# Game_Consol_Power.net
KiCad netlist of a schematic drawn in Altium Designer
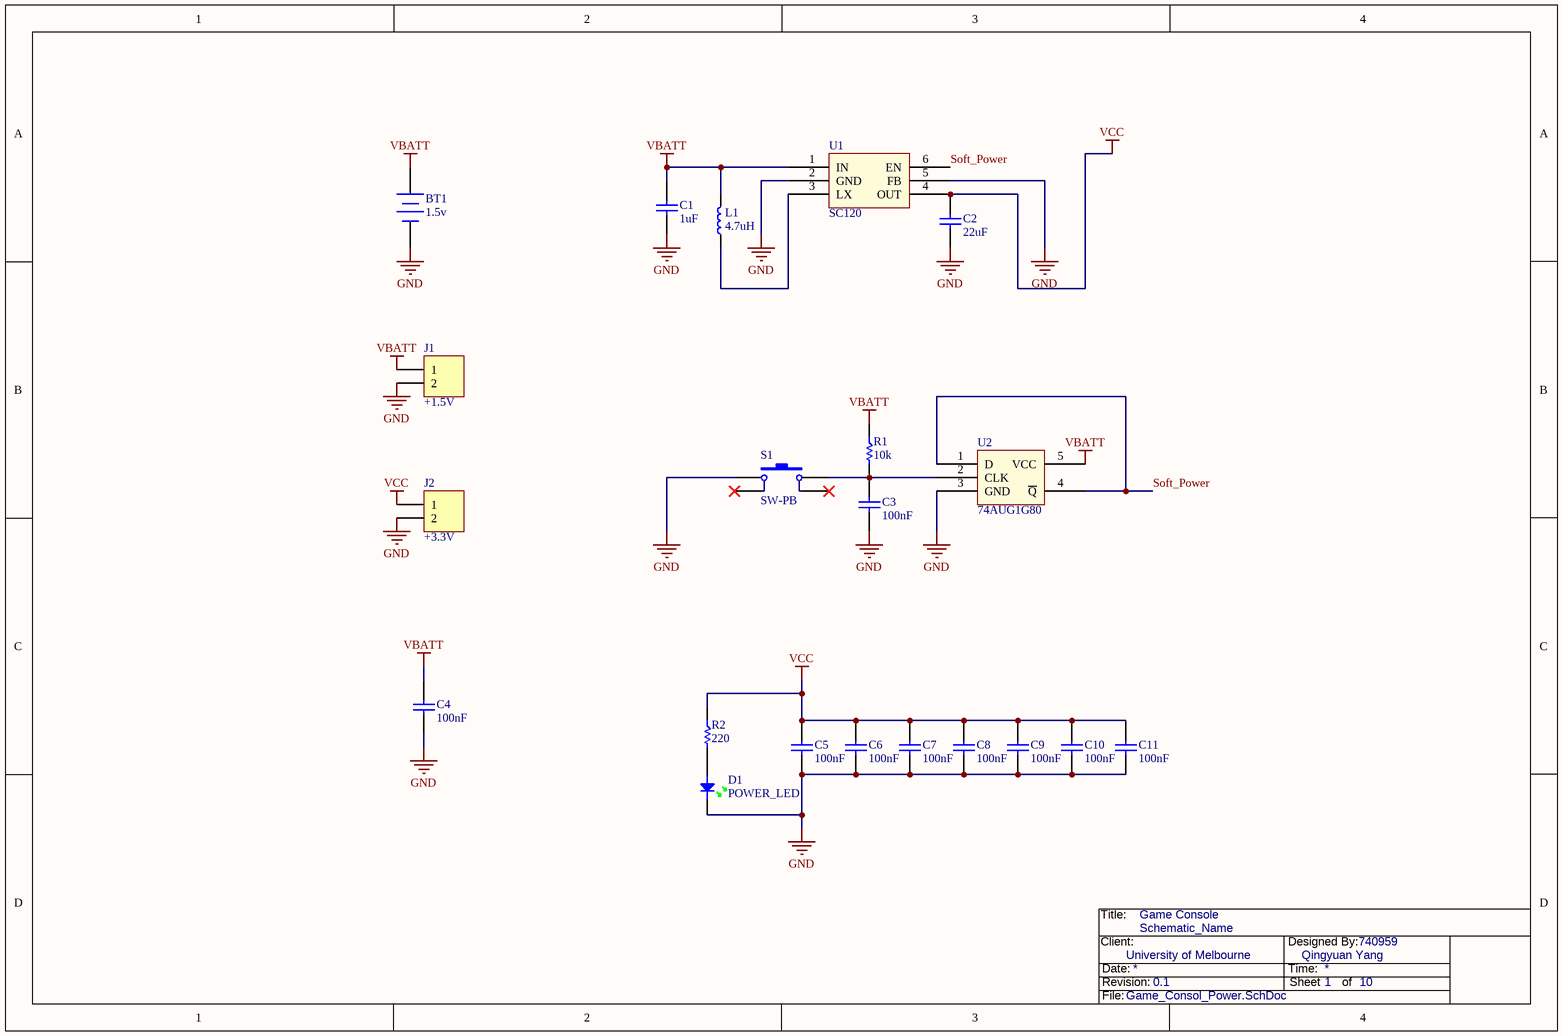
[diagram p0: Game_Consol_Power.SchDoc]

(export (version "E")
  (design (tool "Eeschema 10.0.6"))
  (components
    (comp (ref "BT1")
      (value "1.5v")
      (footprint "BATT_HOLDER")
      (description "Battery Holder AA 1.5v")
      (fields (field (name "PUBLISHER") "Altium Limited"))
      (libsource (lib "EmbSD Lib 0v1") (part "BAT"))
    )
    (comp (ref "C1")
      (value "1uF")
      (footprint "0805")
      (description "Capacitor 100nF")
      (libsource (lib "EmbSD Lib 0v1") (part "C 0805"))
    )
    (comp (ref "C2")
      (value "22uF")
      (footprint "1210")
      (description "Capacitor 22uF")
      (fields
        (field (name "MANUFACTURER") "Generic Components")
        (field (name "MANUFACTURER PART NUMBER") "LMK316F226ZL-T")
        (field (name "PUBLISHER") "Altium Limited")
      )
      (libsource (lib "EmbSD Lib 0v1") (part "C 1210"))
    )
    (comp (ref "C3")
      (value "100nF")
      (footprint "0805")
      (description "Capacitor 100nF")
      (libsource (lib "EmbSD Lib 0v1") (part "C 0805"))
    )
    (comp (ref "C4")
      (value "100nF")
      (footprint "0805")
      (description "Capacitor 100nF")
      (libsource (lib "EmbSD Lib 0v1") (part "C 0805"))
    )
    (comp (ref "C5")
      (value "100nF")
      (footprint "0805")
      (description "Capacitor 100nF")
      (libsource (lib "EmbSD Lib 0v1") (part "C 0805"))
    )
    (comp (ref "C6")
      (value "100nF")
      (footprint "0805")
      (description "Capacitor 100nF")
      (libsource (lib "EmbSD Lib 0v1") (part "C 0805"))
    )
    (comp (ref "C7")
      (value "100nF")
      (footprint "0805")
      (description "Capacitor 100nF")
      (libsource (lib "EmbSD Lib 0v1") (part "C 0805"))
    )
    (comp (ref "C8")
      (value "100nF")
      (footprint "0805")
      (description "Capacitor 100nF")
      (libsource (lib "EmbSD Lib 0v1") (part "C 0805"))
    )
    (comp (ref "C9")
      (value "100nF")
      (footprint "0805")
      (description "Capacitor 100nF")
      (libsource (lib "EmbSD Lib 0v1") (part "C 0805"))
    )
    (comp (ref "C10")
      (value "100nF")
      (footprint "0805")
      (description "Capacitor 100nF")
      (libsource (lib "EmbSD Lib 0v1") (part "C 0805"))
    )
    (comp (ref "C11")
      (value "100nF")
      (footprint "0805")
      (description "Capacitor 100nF")
      (libsource (lib "EmbSD Lib 0v1") (part "C 0805"))
    )
    (comp (ref "D1")
      (value "POWER_LED")
      (footprint "0805D")
      (description "Light Emitting Diode")
      (fields (field (name "MANUFACTURER") "Generic Components") (field (name "PUBLISHER") "Altium Limited"))
      (libsource (lib "EmbSD Lib 0v1") (part "LED GREEN"))
    )
    (comp (ref "J1")
      (value "+1.5V")
      (footprint "HDR1X2")
      (description "Header, 2-Pin")
      (fields (field (name "PUBLISHER") "Altium Limited"))
      (libsource (lib "Miscellaneous Connectors") (part "Header 2"))
    )
    (comp (ref "J2")
      (value "+3.3V")
      (footprint "HDR1X2")
      (description "Header, 2-Pin")
      (fields (field (name "PUBLISHER") "Altium Limited"))
      (libsource (lib "Miscellaneous Connectors") (part "Header 2"))
    )
    (comp (ref "L1")
      (value "4.7uH")
      (footprint "1210L")
      (description "Inductor 4.7uH")
      (fields
        (field (name "MANUFACTURER") "Murata Electronics North America")
        (field (name "MANUFACTURER PART NUMBER") "LQH32CN4R7M23L")
        (field (name "PUBLISHER") "Altium Limited")
      )
      (libsource (lib "EmbSD Lib 0v1") (part "I 1210"))
    )
    (comp (ref "R1")
      (value "10k")
      (footprint "0805")
      (description "Resistor")
      (libsource (lib "EmbSD Lib 0v1") (part "R"))
    )
    (comp (ref "R2")
      (value "220")
      (footprint "0805")
      (description "Resistor")
      (libsource (lib "EmbSD Lib 0v1") (part "R"))
    )
    (comp (ref "S1")
      (value "SW-PB")
      (footprint "SPNO_SMD")
      (description "Push Button Switch")
      (fields
        (field (name "MANUFACTURER") "TE Connectivity")
        (field (name "MANUFACTURER PART NUMBER") "FSM4JSMA")
        (field (name "PUBLISHER") "Altium Limited")
      )
      (libsource (lib "EmbSD Lib 0v1") (part "SW-PB"))
    )
    (comp (ref "U1")
      (value "SC120")
      (footprint "SOT23-6")
      (description "Regulator Low Voltage")
      (libsource (lib "EmbSD Lib 0v1") (part "SC120"))
    )
    (comp (ref "U2")
      (value "74AUG1G80")
      (footprint "SOT23-5")
      (description "Inverted single D flip flop")
      (libsource (lib "EmbSD Lib 0v1") (part "74AUG1G80"))
    )
  )
  (nets
    (net (code "1") (name "/Soft_Power") (class "Default")
      (node (ref "U1") (pin "6") (pinfunction "EN_6") (pintype "passive"))
      (node (ref "U2") (pin "1") (pinfunction "D_1") (pintype "passive"))
      (node (ref "U2") (pin "4") (pinfunction "~{Q}_4") (pintype "passive"))
    )
    (net (code "2") (name "GND") (class "Default")
      (node (ref "BT1") (pin "2") (pinfunction "-_2") (pintype "passive"))
      (node (ref "C1") (pin "2") (pinfunction "2_2") (pintype "passive"))
      (node (ref "C10") (pin "2") (pinfunction "2_2") (pintype "passive"))
      (node (ref "C11") (pin "2") (pinfunction "2_2") (pintype "passive"))
      (node (ref "C2") (pin "2") (pinfunction "2_2") (pintype "passive"))
      (node (ref "C3") (pin "2") (pinfunction "2_2") (pintype "passive"))
      (node (ref "C4") (pin "2") (pinfunction "2_2") (pintype "passive"))
      (node (ref "C5") (pin "2") (pinfunction "2_2") (pintype "passive"))
      (node (ref "C6") (pin "2") (pinfunction "2_2") (pintype "passive"))
      (node (ref "C7") (pin "2") (pinfunction "2_2") (pintype "passive"))
      (node (ref "C8") (pin "2") (pinfunction "2_2") (pintype "passive"))
      (node (ref "C9") (pin "2") (pinfunction "2_2") (pintype "passive"))
      (node (ref "D1") (pin "K") (pinfunction "K_K") (pintype "passive"))
      (node (ref "J1") (pin "2") (pinfunction "2_2") (pintype "passive"))
      (node (ref "J2") (pin "2") (pinfunction "2_2") (pintype "passive"))
      (node (ref "S1") (pin "1") (pinfunction "1_1") (pintype "passive"))
      (node (ref "U1") (pin "2") (pinfunction "GND_2") (pintype "passive"))
      (node (ref "U1") (pin "5") (pinfunction "FB_5") (pintype "passive"))
      (node (ref "U2") (pin "3") (pinfunction "GND_3") (pintype "passive"))
    )
    (net (code "3") (name "Net-(D1-PadA)") (class "Default")
      (node (ref "D1") (pin "A") (pinfunction "A_A") (pintype "passive"))
      (node (ref "R2") (pin "2") (pintype "passive"))
    )
    (net (code "4") (name "Net-(U1-LX)") (class "Default")
      (node (ref "L1") (pin "1") (pinfunction "1_1") (pintype "passive"))
      (node (ref "U1") (pin "3") (pinfunction "LX_3") (pintype "passive"))
    )
    (net (code "5") (name "Net-(U2-CLK)") (class "Default")
      (node (ref "C3") (pin "1") (pinfunction "1_1") (pintype "passive"))
      (node (ref "R1") (pin "2") (pintype "passive"))
      (node (ref "S1") (pin "3") (pinfunction "3_3") (pintype "passive"))
      (node (ref "U2") (pin "2") (pinfunction "CLK_2") (pintype "passive"))
    )
    (net (code "6") (name "VBATT") (class "Default")
      (node (ref "BT1") (pin "1") (pinfunction "+_1") (pintype "passive"))
      (node (ref "C1") (pin "1") (pinfunction "1_1") (pintype "passive"))
      (node (ref "C4") (pin "1") (pinfunction "1_1") (pintype "passive"))
      (node (ref "J1") (pin "1") (pinfunction "1_1") (pintype "passive"))
      (node (ref "L1") (pin "2") (pinfunction "2_2") (pintype "passive"))
      (node (ref "R1") (pin "1") (pintype "passive"))
      (node (ref "U1") (pin "1") (pinfunction "IN_1") (pintype "passive"))
      (node (ref "U2") (pin "5") (pinfunction "VCC_5") (pintype "passive"))
    )
    (net (code "7") (name "VCC") (class "Default")
      (node (ref "C10") (pin "1") (pinfunction "1_1") (pintype "passive"))
      (node (ref "C11") (pin "1") (pinfunction "1_1") (pintype "passive"))
      (node (ref "C2") (pin "1") (pinfunction "1_1") (pintype "passive"))
      (node (ref "C5") (pin "1") (pinfunction "1_1") (pintype "passive"))
      (node (ref "C6") (pin "1") (pinfunction "1_1") (pintype "passive"))
      (node (ref "C7") (pin "1") (pinfunction "1_1") (pintype "passive"))
      (node (ref "C8") (pin "1") (pinfunction "1_1") (pintype "passive"))
      (node (ref "C9") (pin "1") (pinfunction "1_1") (pintype "passive"))
      (node (ref "J2") (pin "1") (pinfunction "1_1") (pintype "passive"))
      (node (ref "R2") (pin "1") (pintype "passive"))
      (node (ref "U1") (pin "4") (pinfunction "OUT_4") (pintype "passive"))
    )
    (net (code "8") (name "unconnected-(S1-Pad2)") (class "Default")
      (node (ref "S1") (pin "2") (pinfunction "2_2") (pintype "passive+no_connect"))
    )
    (net (code "9") (name "unconnected-(S1-Pad4)") (class "Default")
      (node (ref "S1") (pin "4") (pinfunction "4_4") (pintype "passive+no_connect"))
    )
  )
)
